# 9Mux_v5.net
KiCad netlist of a schematic drawn in EAGLE
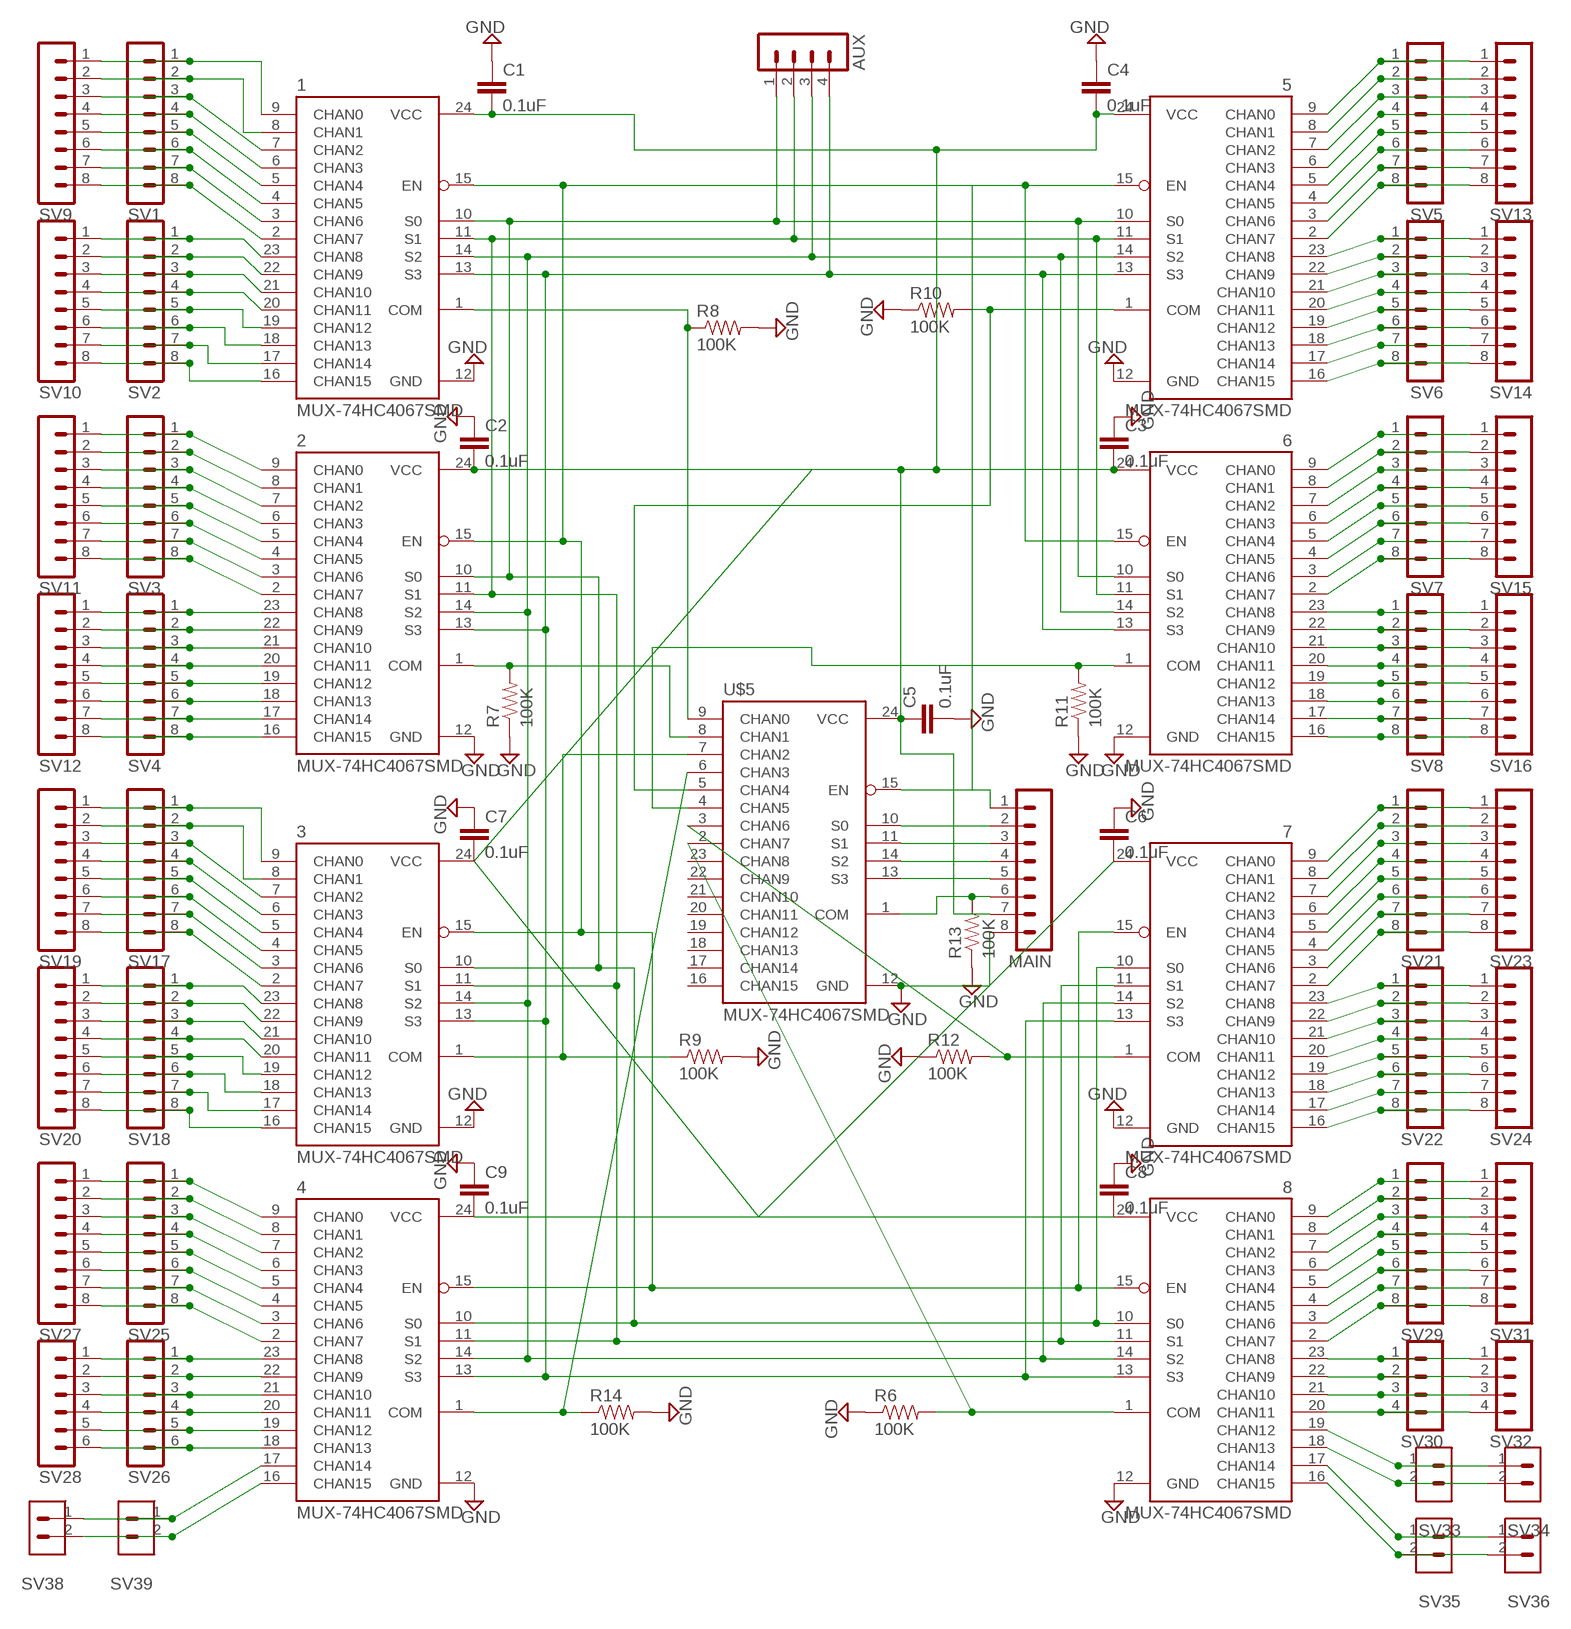
[diagram p0: schematic, sheet 1]

(export (version "E")
  (design (tool "Eeschema 10.0.6"))
  (components
    (comp (ref "1")
      (value "MUX-74HC4067SMD")
      (footprint "eagle-import:SSOP24")
      (libsource (lib "eagle-import") (part "MUX-74HC4067SMD"))
    )
    (comp (ref "2")
      (value "MUX-74HC4067SMD")
      (footprint "eagle-import:SSOP24")
      (libsource (lib "eagle-import") (part "MUX-74HC4067SMD"))
    )
    (comp (ref "3")
      (value "MUX-74HC4067SMD")
      (footprint "eagle-import:SSOP24")
      (libsource (lib "eagle-import") (part "MUX-74HC4067SMD"))
    )
    (comp (ref "4")
      (value "MUX-74HC4067SMD")
      (footprint "eagle-import:SSOP24")
      (libsource (lib "eagle-import") (part "MUX-74HC4067SMD"))
    )
    (comp (ref "5")
      (value "MUX-74HC4067SMD")
      (footprint "eagle-import:SSOP24")
      (libsource (lib "eagle-import") (part "MUX-74HC4067SMD"))
    )
    (comp (ref "6")
      (value "MUX-74HC4067SMD")
      (footprint "eagle-import:SSOP24")
      (libsource (lib "eagle-import") (part "MUX-74HC4067SMD"))
    )
    (comp (ref "7")
      (value "MUX-74HC4067SMD")
      (footprint "eagle-import:SSOP24")
      (libsource (lib "eagle-import") (part "MUX-74HC4067SMD"))
    )
    (comp (ref "8")
      (value "MUX-74HC4067SMD")
      (footprint "eagle-import:SSOP24")
      (libsource (lib "eagle-import") (part "MUX-74HC4067SMD"))
    )
    (comp (ref "AUX")
      (value "MA04-1")
      (footprint "eagle-import:MA04-1")
      (libsource (lib "eagle-import") (part "MA04-1"))
    )
    (comp (ref "C1")
      (value "0.1uF")
      (footprint "eagle-import:0603-CAP")
      (libsource (lib "eagle-import") (part "CAP0603-CAP"))
    )
    (comp (ref "C2")
      (value "0.1uF")
      (footprint "eagle-import:0603-CAP")
      (libsource (lib "eagle-import") (part "CAP0603-CAP"))
    )
    (comp (ref "C3")
      (value "0.1uF")
      (footprint "eagle-import:0603-CAP")
      (libsource (lib "eagle-import") (part "CAP0603-CAP"))
    )
    (comp (ref "C4")
      (value "0.1uF")
      (footprint "eagle-import:0603-CAP")
      (libsource (lib "eagle-import") (part "CAP0603-CAP"))
    )
    (comp (ref "C5")
      (value "0.1uF")
      (footprint "eagle-import:0603-CAP")
      (libsource (lib "eagle-import") (part "CAP0603-CAP"))
    )
    (comp (ref "C6")
      (value "0.1uF")
      (footprint "eagle-import:0603-CAP")
      (libsource (lib "eagle-import") (part "CAP0603-CAP"))
    )
    (comp (ref "C7")
      (value "0.1uF")
      (footprint "eagle-import:0603-CAP")
      (libsource (lib "eagle-import") (part "CAP0603-CAP"))
    )
    (comp (ref "C8")
      (value "0.1uF")
      (footprint "eagle-import:0603-CAP")
      (libsource (lib "eagle-import") (part "CAP0603-CAP"))
    )
    (comp (ref "C9")
      (value "0.1uF")
      (footprint "eagle-import:0603-CAP")
      (libsource (lib "eagle-import") (part "CAP0603-CAP"))
    )
    (comp (ref "MAIN")
      (value "MA08-1")
      (footprint "eagle-import:MA08-1")
      (libsource (lib "eagle-import") (part "MA08-1"))
    )
    (comp (ref "R6")
      (value "100K")
      (footprint "eagle-import:0603-RES")
      (libsource (lib "eagle-import") (part "RESISTOR0603"))
    )
    (comp (ref "R7")
      (value "100K")
      (footprint "eagle-import:0603-RES")
      (libsource (lib "eagle-import") (part "RESISTOR0603"))
    )
    (comp (ref "R8")
      (value "100K")
      (footprint "eagle-import:0603-RES")
      (libsource (lib "eagle-import") (part "RESISTOR0603"))
    )
    (comp (ref "R9")
      (value "100K")
      (footprint "eagle-import:0603-RES")
      (libsource (lib "eagle-import") (part "RESISTOR0603"))
    )
    (comp (ref "R10")
      (value "100K")
      (footprint "eagle-import:0603-RES")
      (libsource (lib "eagle-import") (part "RESISTOR0603"))
    )
    (comp (ref "R11")
      (value "100K")
      (footprint "eagle-import:0603-RES")
      (libsource (lib "eagle-import") (part "RESISTOR0603"))
    )
    (comp (ref "R12")
      (value "100K")
      (footprint "eagle-import:0603-RES")
      (libsource (lib "eagle-import") (part "RESISTOR0603"))
    )
    (comp (ref "R13")
      (value "100K")
      (footprint "eagle-import:0603-RES")
      (libsource (lib "eagle-import") (part "RESISTOR0603"))
    )
    (comp (ref "R14")
      (value "100K")
      (footprint "eagle-import:0603-RES")
      (libsource (lib "eagle-import") (part "RESISTOR0603"))
    )
    (comp (ref "SV1")
      (value "MA08-1")
      (footprint "eagle-import:MA08-1")
      (libsource (lib "eagle-import") (part "MA08-1"))
    )
    (comp (ref "SV2")
      (value "MA08-1")
      (footprint "eagle-import:MA08-1")
      (libsource (lib "eagle-import") (part "MA08-1"))
    )
    (comp (ref "SV3")
      (value "MA08-1")
      (footprint "eagle-import:MA08-1")
      (libsource (lib "eagle-import") (part "MA08-1"))
    )
    (comp (ref "SV4")
      (value "MA08-1")
      (footprint "eagle-import:MA08-1")
      (libsource (lib "eagle-import") (part "MA08-1"))
    )
    (comp (ref "SV5")
      (value "MA08-1")
      (footprint "eagle-import:MA08-1")
      (libsource (lib "eagle-import") (part "MA08-1"))
    )
    (comp (ref "SV6")
      (value "MA08-1")
      (footprint "eagle-import:MA08-1")
      (libsource (lib "eagle-import") (part "MA08-1"))
    )
    (comp (ref "SV7")
      (value "MA08-1")
      (footprint "eagle-import:MA08-1")
      (libsource (lib "eagle-import") (part "MA08-1"))
    )
    (comp (ref "SV8")
      (value "MA08-1")
      (footprint "eagle-import:MA08-1")
      (libsource (lib "eagle-import") (part "MA08-1"))
    )
    (comp (ref "SV9")
      (value "MA08-1")
      (footprint "eagle-import:MA08-1")
      (libsource (lib "eagle-import") (part "MA08-1"))
    )
    (comp (ref "SV10")
      (value "MA08-1")
      (footprint "eagle-import:MA08-1")
      (libsource (lib "eagle-import") (part "MA08-1"))
    )
    (comp (ref "SV11")
      (value "MA08-1")
      (footprint "eagle-import:MA08-1")
      (libsource (lib "eagle-import") (part "MA08-1"))
    )
    (comp (ref "SV12")
      (value "MA08-1")
      (footprint "eagle-import:MA08-1")
      (libsource (lib "eagle-import") (part "MA08-1"))
    )
    (comp (ref "SV13")
      (value "MA08-1")
      (footprint "eagle-import:MA08-1")
      (libsource (lib "eagle-import") (part "MA08-1"))
    )
    (comp (ref "SV14")
      (value "MA08-1")
      (footprint "eagle-import:MA08-1")
      (libsource (lib "eagle-import") (part "MA08-1"))
    )
    (comp (ref "SV15")
      (value "MA08-1")
      (footprint "eagle-import:MA08-1")
      (libsource (lib "eagle-import") (part "MA08-1"))
    )
    (comp (ref "SV16")
      (value "MA08-1")
      (footprint "eagle-import:MA08-1")
      (libsource (lib "eagle-import") (part "MA08-1"))
    )
    (comp (ref "SV17")
      (value "MA08-1")
      (footprint "eagle-import:MA08-1")
      (libsource (lib "eagle-import") (part "MA08-1"))
    )
    (comp (ref "SV18")
      (value "MA08-1")
      (footprint "eagle-import:MA08-1")
      (libsource (lib "eagle-import") (part "MA08-1"))
    )
    (comp (ref "SV19")
      (value "MA08-1")
      (footprint "eagle-import:MA08-1")
      (libsource (lib "eagle-import") (part "MA08-1"))
    )
    (comp (ref "SV20")
      (value "MA08-1")
      (footprint "eagle-import:MA08-1")
      (libsource (lib "eagle-import") (part "MA08-1"))
    )
    (comp (ref "SV21")
      (value "MA08-1")
      (footprint "eagle-import:MA08-1")
      (libsource (lib "eagle-import") (part "MA08-1"))
    )
    (comp (ref "SV22")
      (value "MA08-1")
      (footprint "eagle-import:MA08-1")
      (libsource (lib "eagle-import") (part "MA08-1"))
    )
    (comp (ref "SV23")
      (value "MA08-1")
      (footprint "eagle-import:MA08-1")
      (libsource (lib "eagle-import") (part "MA08-1"))
    )
    (comp (ref "SV24")
      (value "MA08-1")
      (footprint "eagle-import:MA08-1")
      (libsource (lib "eagle-import") (part "MA08-1"))
    )
    (comp (ref "SV25")
      (value "MA08-1")
      (footprint "eagle-import:MA08-1")
      (libsource (lib "eagle-import") (part "MA08-1"))
    )
    (comp (ref "SV26")
      (value "MA06-1")
      (footprint "eagle-import:MA06-1")
      (libsource (lib "eagle-import") (part "MA06-1"))
    )
    (comp (ref "SV27")
      (value "MA08-1")
      (footprint "eagle-import:MA08-1")
      (libsource (lib "eagle-import") (part "MA08-1"))
    )
    (comp (ref "SV28")
      (value "MA06-1")
      (footprint "eagle-import:MA06-1")
      (libsource (lib "eagle-import") (part "MA06-1"))
    )
    (comp (ref "SV29")
      (value "MA08-1")
      (footprint "eagle-import:MA08-1")
      (libsource (lib "eagle-import") (part "MA08-1"))
    )
    (comp (ref "SV30")
      (value "MA04-1")
      (footprint "eagle-import:MA04-1")
      (libsource (lib "eagle-import") (part "MA04-1"))
    )
    (comp (ref "SV31")
      (value "MA08-1")
      (footprint "eagle-import:MA08-1")
      (libsource (lib "eagle-import") (part "MA08-1"))
    )
    (comp (ref "SV32")
      (value "MA04-1")
      (footprint "eagle-import:MA04-1")
      (libsource (lib "eagle-import") (part "MA04-1"))
    )
    (comp (ref "SV33")
      (value "MA02-1")
      (footprint "eagle-import:MA03-1")
      (libsource (lib "eagle-import") (part "MA02-1"))
    )
    (comp (ref "SV34")
      (value "MA02-1")
      (footprint "eagle-import:MA03-1")
      (libsource (lib "eagle-import") (part "MA02-1"))
    )
    (comp (ref "SV35")
      (value "MA02-1")
      (footprint "eagle-import:MA03-1")
      (libsource (lib "eagle-import") (part "MA02-1"))
    )
    (comp (ref "SV36")
      (value "MA02-1")
      (footprint "eagle-import:MA03-1")
      (libsource (lib "eagle-import") (part "MA02-1"))
    )
    (comp (ref "SV38")
      (value "MA02-1")
      (footprint "eagle-import:MA03-1")
      (libsource (lib "eagle-import") (part "MA02-1"))
    )
    (comp (ref "SV39")
      (value "MA02-1")
      (footprint "eagle-import:MA03-1")
      (libsource (lib "eagle-import") (part "MA02-1"))
    )
    (comp (ref "U$5")
      (value "MUX-74HC4067SMD")
      (footprint "eagle-import:SSOP24")
      (libsource (lib "eagle-import") (part "MUX-74HC4067SMD"))
    )
  )
  (nets
    (net (code "1") (name "GND") (class "Default")
      (node (ref "1") (pin "12") (pinfunction "GND_12") (pintype "bidirectional"))
      (node (ref "2") (pin "12") (pinfunction "GND_12") (pintype "bidirectional"))
      (node (ref "3") (pin "12") (pinfunction "GND_12") (pintype "bidirectional"))
      (node (ref "4") (pin "12") (pinfunction "GND_12") (pintype "bidirectional"))
      (node (ref "5") (pin "12") (pinfunction "GND_12") (pintype "bidirectional"))
      (node (ref "6") (pin "12") (pinfunction "GND_12") (pintype "bidirectional"))
      (node (ref "7") (pin "12") (pinfunction "GND_12") (pintype "bidirectional"))
      (node (ref "8") (pin "12") (pinfunction "GND_12") (pintype "bidirectional"))
      (node (ref "C1") (pin "1") (pinfunction "1_1") (pintype "passive"))
      (node (ref "C2") (pin "1") (pinfunction "1_1") (pintype "passive"))
      (node (ref "C3") (pin "1") (pinfunction "1_1") (pintype "passive"))
      (node (ref "C4") (pin "1") (pinfunction "1_1") (pintype "passive"))
      (node (ref "C5") (pin "2") (pinfunction "2_2") (pintype "passive"))
      (node (ref "C6") (pin "1") (pinfunction "1_1") (pintype "passive"))
      (node (ref "C7") (pin "1") (pinfunction "1_1") (pintype "passive"))
      (node (ref "C8") (pin "1") (pinfunction "1_1") (pintype "passive"))
      (node (ref "C9") (pin "1") (pinfunction "1_1") (pintype "passive"))
      (node (ref "MAIN") (pin "8") (pinfunction "8_8") (pintype "passive"))
      (node (ref "R10") (pin "1") (pinfunction "1_1") (pintype "passive"))
      (node (ref "R11") (pin "1") (pinfunction "1_1") (pintype "passive"))
      (node (ref "R12") (pin "1") (pinfunction "1_1") (pintype "passive"))
      (node (ref "R13") (pin "1") (pinfunction "1_1") (pintype "passive"))
      (node (ref "R14") (pin "2") (pinfunction "2_2") (pintype "passive"))
      (node (ref "R6") (pin "1") (pinfunction "1_1") (pintype "passive"))
      (node (ref "R7") (pin "1") (pinfunction "1_1") (pintype "passive"))
      (node (ref "R8") (pin "2") (pinfunction "2_2") (pintype "passive"))
      (node (ref "R9") (pin "2") (pinfunction "2_2") (pintype "passive"))
      (node (ref "U$5") (pin "12") (pinfunction "GND_12") (pintype "bidirectional"))
    )
    (net (code "2") (name "Net-(1-CHAN0)") (class "Default")
      (node (ref "1") (pin "9") (pinfunction "CHAN0_9") (pintype "bidirectional"))
      (node (ref "SV1") (pin "1") (pinfunction "1_1") (pintype "passive"))
      (node (ref "SV9") (pin "1") (pinfunction "1_1") (pintype "passive"))
    )
    (net (code "3") (name "Net-(1-CHAN1)") (class "Default")
      (node (ref "1") (pin "8") (pinfunction "CHAN1_8") (pintype "bidirectional"))
      (node (ref "SV1") (pin "2") (pinfunction "2_2") (pintype "passive"))
      (node (ref "SV9") (pin "2") (pinfunction "2_2") (pintype "passive"))
    )
    (net (code "4") (name "Net-(1-CHAN2)") (class "Default")
      (node (ref "1") (pin "7") (pinfunction "CHAN2_7") (pintype "bidirectional"))
      (node (ref "SV1") (pin "3") (pinfunction "3_3") (pintype "passive"))
      (node (ref "SV9") (pin "3") (pinfunction "3_3") (pintype "passive"))
    )
    (net (code "5") (name "Net-(1-CHAN3)") (class "Default")
      (node (ref "1") (pin "6") (pinfunction "CHAN3_6") (pintype "bidirectional"))
      (node (ref "SV1") (pin "4") (pinfunction "4_4") (pintype "passive"))
      (node (ref "SV9") (pin "4") (pinfunction "4_4") (pintype "passive"))
    )
    (net (code "6") (name "Net-(1-CHAN4)") (class "Default")
      (node (ref "1") (pin "5") (pinfunction "CHAN4_5") (pintype "bidirectional"))
      (node (ref "SV1") (pin "5") (pinfunction "5_5") (pintype "passive"))
      (node (ref "SV9") (pin "5") (pinfunction "5_5") (pintype "passive"))
    )
    (net (code "7") (name "Net-(1-CHAN5)") (class "Default")
      (node (ref "1") (pin "4") (pinfunction "CHAN5_4") (pintype "bidirectional"))
      (node (ref "SV1") (pin "6") (pinfunction "6_6") (pintype "passive"))
      (node (ref "SV9") (pin "6") (pinfunction "6_6") (pintype "passive"))
    )
    (net (code "8") (name "Net-(1-CHAN6)") (class "Default")
      (node (ref "1") (pin "3") (pinfunction "CHAN6_3") (pintype "bidirectional"))
      (node (ref "SV1") (pin "7") (pinfunction "7_7") (pintype "passive"))
      (node (ref "SV9") (pin "7") (pinfunction "7_7") (pintype "passive"))
    )
    (net (code "9") (name "Net-(1-CHAN7)") (class "Default")
      (node (ref "1") (pin "2") (pinfunction "CHAN7_2") (pintype "bidirectional"))
      (node (ref "SV1") (pin "8") (pinfunction "8_8") (pintype "passive"))
      (node (ref "SV9") (pin "8") (pinfunction "8_8") (pintype "passive"))
    )
    (net (code "10") (name "Net-(1-CHAN8)") (class "Default")
      (node (ref "1") (pin "23") (pinfunction "CHAN8_23") (pintype "bidirectional"))
      (node (ref "SV10") (pin "1") (pinfunction "1_1") (pintype "passive"))
      (node (ref "SV2") (pin "1") (pinfunction "1_1") (pintype "passive"))
    )
    (net (code "11") (name "Net-(1-CHAN9)") (class "Default")
      (node (ref "1") (pin "22") (pinfunction "CHAN9_22") (pintype "bidirectional"))
      (node (ref "SV10") (pin "2") (pinfunction "2_2") (pintype "passive"))
      (node (ref "SV2") (pin "2") (pinfunction "2_2") (pintype "passive"))
    )
    (net (code "12") (name "Net-(1-CHAN10)") (class "Default")
      (node (ref "1") (pin "21") (pinfunction "CHAN10_21") (pintype "bidirectional"))
      (node (ref "SV10") (pin "3") (pinfunction "3_3") (pintype "passive"))
      (node (ref "SV2") (pin "3") (pinfunction "3_3") (pintype "passive"))
    )
    (net (code "13") (name "Net-(1-CHAN11)") (class "Default")
      (node (ref "1") (pin "20") (pinfunction "CHAN11_20") (pintype "bidirectional"))
      (node (ref "SV10") (pin "4") (pinfunction "4_4") (pintype "passive"))
      (node (ref "SV2") (pin "4") (pinfunction "4_4") (pintype "passive"))
    )
    (net (code "14") (name "Net-(1-CHAN12)") (class "Default")
      (node (ref "1") (pin "19") (pinfunction "CHAN12_19") (pintype "bidirectional"))
      (node (ref "SV10") (pin "5") (pinfunction "5_5") (pintype "passive"))
      (node (ref "SV2") (pin "5") (pinfunction "5_5") (pintype "passive"))
    )
    (net (code "15") (name "Net-(1-CHAN13)") (class "Default")
      (node (ref "1") (pin "18") (pinfunction "CHAN13_18") (pintype "bidirectional"))
      (node (ref "SV10") (pin "6") (pinfunction "6_6") (pintype "passive"))
      (node (ref "SV2") (pin "6") (pinfunction "6_6") (pintype "passive"))
    )
    (net (code "16") (name "Net-(1-CHAN14)") (class "Default")
      (node (ref "1") (pin "17") (pinfunction "CHAN14_17") (pintype "bidirectional"))
      (node (ref "SV10") (pin "7") (pinfunction "7_7") (pintype "passive"))
      (node (ref "SV2") (pin "7") (pinfunction "7_7") (pintype "passive"))
    )
    (net (code "17") (name "Net-(1-CHAN15)") (class "Default")
      (node (ref "1") (pin "16") (pinfunction "CHAN15_16") (pintype "bidirectional"))
      (node (ref "SV10") (pin "8") (pinfunction "8_8") (pintype "passive"))
      (node (ref "SV2") (pin "8") (pinfunction "8_8") (pintype "passive"))
    )
    (net (code "18") (name "Net-(1-COM)") (class "Default")
      (node (ref "1") (pin "1") (pinfunction "COM_1") (pintype "bidirectional"))
      (node (ref "R8") (pin "1") (pinfunction "1_1") (pintype "passive"))
      (node (ref "U$5") (pin "9") (pinfunction "CHAN0_9") (pintype "bidirectional"))
    )
    (net (code "19") (name "Net-(1-EN)") (class "Default")
      (node (ref "1") (pin "15") (pinfunction "EN_15") (pintype "input"))
      (node (ref "2") (pin "15") (pinfunction "EN_15") (pintype "input"))
      (node (ref "3") (pin "15") (pinfunction "EN_15") (pintype "input"))
      (node (ref "4") (pin "15") (pinfunction "EN_15") (pintype "input"))
      (node (ref "5") (pin "15") (pinfunction "EN_15") (pintype "input"))
      (node (ref "6") (pin "15") (pinfunction "EN_15") (pintype "input"))
      (node (ref "7") (pin "15") (pinfunction "EN_15") (pintype "input"))
      (node (ref "8") (pin "15") (pinfunction "EN_15") (pintype "input"))
      (node (ref "MAIN") (pin "1") (pinfunction "1_1") (pintype "passive"))
      (node (ref "U$5") (pin "15") (pinfunction "EN_15") (pintype "input"))
    )
    (net (code "20") (name "Net-(1-S0)") (class "Default")
      (node (ref "1") (pin "10") (pinfunction "S0_10") (pintype "input"))
      (node (ref "2") (pin "10") (pinfunction "S0_10") (pintype "input"))
      (node (ref "3") (pin "10") (pinfunction "S0_10") (pintype "input"))
      (node (ref "4") (pin "10") (pinfunction "S0_10") (pintype "input"))
      (node (ref "5") (pin "10") (pinfunction "S0_10") (pintype "input"))
      (node (ref "6") (pin "10") (pinfunction "S0_10") (pintype "input"))
      (node (ref "7") (pin "10") (pinfunction "S0_10") (pintype "input"))
      (node (ref "8") (pin "10") (pinfunction "S0_10") (pintype "input"))
      (node (ref "AUX") (pin "1") (pinfunction "1_1") (pintype "passive"))
    )
    (net (code "21") (name "Net-(1-S1)") (class "Default")
      (node (ref "1") (pin "11") (pinfunction "S1_11") (pintype "input"))
      (node (ref "2") (pin "11") (pinfunction "S1_11") (pintype "input"))
      (node (ref "3") (pin "11") (pinfunction "S1_11") (pintype "input"))
      (node (ref "4") (pin "11") (pinfunction "S1_11") (pintype "input"))
      (node (ref "5") (pin "11") (pinfunction "S1_11") (pintype "input"))
      (node (ref "6") (pin "11") (pinfunction "S1_11") (pintype "input"))
      (node (ref "7") (pin "11") (pinfunction "S1_11") (pintype "input"))
      (node (ref "8") (pin "11") (pinfunction "S1_11") (pintype "input"))
      (node (ref "AUX") (pin "2") (pinfunction "2_2") (pintype "passive"))
    )
    (net (code "22") (name "Net-(1-S2)") (class "Default")
      (node (ref "1") (pin "14") (pinfunction "S2_14") (pintype "input"))
      (node (ref "2") (pin "14") (pinfunction "S2_14") (pintype "input"))
      (node (ref "3") (pin "14") (pinfunction "S2_14") (pintype "input"))
      (node (ref "4") (pin "14") (pinfunction "S2_14") (pintype "input"))
      (node (ref "5") (pin "14") (pinfunction "S2_14") (pintype "input"))
      (node (ref "6") (pin "14") (pinfunction "S2_14") (pintype "input"))
      (node (ref "7") (pin "14") (pinfunction "S2_14") (pintype "input"))
      (node (ref "8") (pin "14") (pinfunction "S2_14") (pintype "input"))
      (node (ref "AUX") (pin "3") (pinfunction "3_3") (pintype "passive"))
    )
    (net (code "23") (name "Net-(1-S3)") (class "Default")
      (node (ref "1") (pin "13") (pinfunction "S3_13") (pintype "input"))
      (node (ref "2") (pin "13") (pinfunction "S3_13") (pintype "input"))
      (node (ref "3") (pin "13") (pinfunction "S3_13") (pintype "input"))
      (node (ref "4") (pin "13") (pinfunction "S3_13") (pintype "input"))
      (node (ref "5") (pin "13") (pinfunction "S3_13") (pintype "input"))
      (node (ref "6") (pin "13") (pinfunction "S3_13") (pintype "input"))
      (node (ref "7") (pin "13") (pinfunction "S3_13") (pintype "input"))
      (node (ref "8") (pin "13") (pinfunction "S3_13") (pintype "input"))
      (node (ref "AUX") (pin "4") (pinfunction "4_4") (pintype "passive"))
    )
    (net (code "24") (name "Net-(1-VCC)") (class "Default")
      (node (ref "1") (pin "24") (pinfunction "VCC_24") (pintype "bidirectional"))
      (node (ref "2") (pin "24") (pinfunction "VCC_24") (pintype "bidirectional"))
      (node (ref "3") (pin "24") (pinfunction "VCC_24") (pintype "bidirectional"))
      (node (ref "4") (pin "24") (pinfunction "VCC_24") (pintype "bidirectional"))
      (node (ref "5") (pin "24") (pinfunction "VCC_24") (pintype "bidirectional"))
      (node (ref "6") (pin "24") (pinfunction "VCC_24") (pintype "bidirectional"))
      (node (ref "7") (pin "24") (pinfunction "VCC_24") (pintype "bidirectional"))
      (node (ref "8") (pin "24") (pinfunction "VCC_24") (pintype "bidirectional"))
      (node (ref "C1") (pin "2") (pinfunction "2_2") (pintype "passive"))
      (node (ref "C2") (pin "2") (pinfunction "2_2") (pintype "passive"))
      (node (ref "C3") (pin "2") (pinfunction "2_2") (pintype "passive"))
      (node (ref "C4") (pin "2") (pinfunction "2_2") (pintype "passive"))
      (node (ref "C5") (pin "1") (pinfunction "1_1") (pintype "passive"))
      (node (ref "C6") (pin "2") (pinfunction "2_2") (pintype "passive"))
      (node (ref "C7") (pin "2") (pinfunction "2_2") (pintype "passive"))
      (node (ref "C8") (pin "2") (pinfunction "2_2") (pintype "passive"))
      (node (ref "C9") (pin "2") (pinfunction "2_2") (pintype "passive"))
      (node (ref "MAIN") (pin "7") (pinfunction "7_7") (pintype "passive"))
      (node (ref "U$5") (pin "24") (pinfunction "VCC_24") (pintype "bidirectional"))
    )
    (net (code "25") (name "Net-(2-CHAN0)") (class "Default")
      (node (ref "2") (pin "9") (pinfunction "CHAN0_9") (pintype "bidirectional"))
      (node (ref "SV11") (pin "1") (pinfunction "1_1") (pintype "passive"))
      (node (ref "SV3") (pin "1") (pinfunction "1_1") (pintype "passive"))
    )
    (net (code "26") (name "Net-(2-CHAN1)") (class "Default")
      (node (ref "2") (pin "8") (pinfunction "CHAN1_8") (pintype "bidirectional"))
      (node (ref "SV11") (pin "2") (pinfunction "2_2") (pintype "passive"))
      (node (ref "SV3") (pin "2") (pinfunction "2_2") (pintype "passive"))
    )
    (net (code "27") (name "Net-(2-CHAN2)") (class "Default")
      (node (ref "2") (pin "7") (pinfunction "CHAN2_7") (pintype "bidirectional"))
      (node (ref "SV11") (pin "3") (pinfunction "3_3") (pintype "passive"))
      (node (ref "SV3") (pin "3") (pinfunction "3_3") (pintype "passive"))
    )
    (net (code "28") (name "Net-(2-CHAN3)") (class "Default")
      (node (ref "2") (pin "6") (pinfunction "CHAN3_6") (pintype "bidirectional"))
      (node (ref "SV11") (pin "4") (pinfunction "4_4") (pintype "passive"))
      (node (ref "SV3") (pin "4") (pinfunction "4_4") (pintype "passive"))
    )
    (net (code "29") (name "Net-(2-CHAN4)") (class "Default")
      (node (ref "2") (pin "5") (pinfunction "CHAN4_5") (pintype "bidirectional"))
      (node (ref "SV11") (pin "5") (pinfunction "5_5") (pintype "passive"))
      (node (ref "SV3") (pin "5") (pinfunction "5_5") (pintype "passive"))
    )
    (net (code "30") (name "Net-(2-CHAN5)") (class "Default")
      (node (ref "2") (pin "4") (pinfunction "CHAN5_4") (pintype "bidirectional"))
      (node (ref "SV11") (pin "6") (pinfunction "6_6") (pintype "passive"))
      (node (ref "SV3") (pin "6") (pinfunction "6_6") (pintype "passive"))
    )
    (net (code "31") (name "Net-(2-CHAN6)") (class "Default")
      (node (ref "2") (pin "3") (pinfunction "CHAN6_3") (pintype "bidirectional"))
      (node (ref "SV11") (pin "7") (pinfunction "7_7") (pintype "passive"))
      (node (ref "SV3") (pin "7") (pinfunction "7_7") (pintype "passive"))
    )
    (net (code "32") (name "Net-(2-CHAN7)") (class "Default")
      (node (ref "2") (pin "2") (pinfunction "CHAN7_2") (pintype "bidirectional"))
      (node (ref "SV11") (pin "8") (pinfunction "8_8") (pintype "passive"))
      (node (ref "SV3") (pin "8") (pinfunction "8_8") (pintype "passive"))
    )
    (net (code "33") (name "Net-(2-CHAN8)") (class "Default")
      (node (ref "2") (pin "23") (pinfunction "CHAN8_23") (pintype "bidirectional"))
      (node (ref "SV12") (pin "1") (pinfunction "1_1") (pintype "passive"))
      (node (ref "SV4") (pin "1") (pinfunction "1_1") (pintype "passive"))
    )
    (net (code "34") (name "Net-(2-CHAN9)") (class "Default")
      (node (ref "2") (pin "22") (pinfunction "CHAN9_22") (pintype "bidirectional"))
      (node (ref "SV12") (pin "2") (pinfunction "2_2") (pintype "passive"))
      (node (ref "SV4") (pin "2") (pinfunction "2_2") (pintype "passive"))
    )
    (net (code "35") (name "Net-(2-CHAN10)") (class "Default")
      (node (ref "2") (pin "21") (pinfunction "CHAN10_21") (pintype "bidirectional"))
      (node (ref "SV12") (pin "3") (pinfunction "3_3") (pintype "passive"))
      (node (ref "SV4") (pin "3") (pinfunction "3_3") (pintype "passive"))
    )
    (net (code "36") (name "Net-(2-CHAN11)") (class "Default")
      (node (ref "2") (pin "20") (pinfunction "CHAN11_20") (pintype "bidirectional"))
      (node (ref "SV12") (pin "4") (pinfunction "4_4") (pintype "passive"))
      (node (ref "SV4") (pin "4") (pinfunction "4_4") (pintype "passive"))
    )
    (net (code "37") (name "Net-(2-CHAN12)") (class "Default")
      (node (ref "2") (pin "19") (pinfunction "CHAN12_19") (pintype "bidirectional"))
      (node (ref "SV12") (pin "5") (pinfunction "5_5") (pintype "passive"))
      (node (ref "SV4") (pin "5") (pinfunction "5_5") (pintype "passive"))
    )
    (net (code "38") (name "Net-(2-CHAN13)") (class "Default")
      (node (ref "2") (pin "18") (pinfunction "CHAN13_18") (pintype "bidirectional"))
      (node (ref "SV12") (pin "6") (pinfunction "6_6") (pintype "passive"))
      (node (ref "SV4") (pin "6") (pinfunction "6_6") (pintype "passive"))
    )
    (net (code "39") (name "Net-(2-CHAN14)") (class "Default")
      (node (ref "2") (pin "17") (pinfunction "CHAN14_17") (pintype "bidirectional"))
      (node (ref "SV12") (pin "7") (pinfunction "7_7") (pintype "passive"))
      (node (ref "SV4") (pin "7") (pinfunction "7_7") (pintype "passive"))
    )
    (net (code "40") (name "Net-(2-CHAN15)") (class "Default")
      (node (ref "2") (pin "16") (pinfunction "CHAN15_16") (pintype "bidirectional"))
      (node (ref "SV12") (pin "8") (pinfunction "8_8") (pintype "passive"))
      (node (ref "SV4") (pin "8") (pinfunction "8_8") (pintype "passive"))
    )
    (net (code "41") (name "Net-(2-COM)") (class "Default")
      (node (ref "2") (pin "1") (pinfunction "COM_1") (pintype "bidirectional"))
      (node (ref "R7") (pin "2") (pinfunction "2_2") (pintype "passive"))
      (node (ref "U$5") (pin "8") (pinfunction "CHAN1_8") (pintype "bidirectional"))
    )
    (net (code "42") (name "Net-(3-CHAN0)") (class "Default")
      (node (ref "3") (pin "9") (pinfunction "CHAN0_9") (pintype "bidirectional"))
      (node (ref "SV17") (pin "1") (pinfunction "1_1") (pintype "passive"))
      (node (ref "SV19") (pin "1") (pinfunction "1_1") (pintype "passive"))
    )
    (net (code "43") (name "Net-(3-CHAN1)") (class "Default")
      (node (ref "3") (pin "8") (pinfunction "CHAN1_8") (pintype "bidirectional"))
      (node (ref "SV17") (pin "2") (pinfunction "2_2") (pintype "passive"))
      (node (ref "SV19") (pin "2") (pinfunction "2_2") (pintype "passive"))
    )
    (net (code "44") (name "Net-(3-CHAN2)") (class "Default")
      (node (ref "3") (pin "7") (pinfunction "CHAN2_7") (pintype "bidirectional"))
      (node (ref "SV17") (pin "3") (pinfunction "3_3") (pintype "passive"))
      (node (ref "SV19") (pin "3") (pinfunction "3_3") (pintype "passive"))
    )
    (net (code "45") (name "Net-(3-CHAN3)") (class "Default")
      (node (ref "3") (pin "6") (pinfunction "CHAN3_6") (pintype "bidirectional"))
      (node (ref "SV17") (pin "4") (pinfunction "4_4") (pintype "passive"))
      (node (ref "SV19") (pin "4") (pinfunction "4_4") (pintype "passive"))
    )
    (net (code "46") (name "Net-(3-CHAN4)") (class "Default")
      (node (ref "3") (pin "5") (pinfunction "CHAN4_5") (pintype "bidirectional"))
      (node (ref "SV17") (pin "5") (pinfunction "5_5") (pintype "passive"))
      (node (ref "SV19") (pin "5") (pinfunction "5_5") (pintype "passive"))
    )
    (net (code "47") (name "Net-(3-CHAN5)") (class "Default")
      (node (ref "3") (pin "4") (pinfunction "CHAN5_4") (pintype "bidirectional"))
      (node (ref "SV17") (pin "6") (pinfunction "6_6") (pintype "passive"))
      (node (ref "SV19") (pin "6") (pinfunction "6_6") (pintype "passive"))
    )
    (net (code "48") (name "Net-(3-CHAN6)") (class "Default")
      (node (ref "3") (pin "3") (pinfunction "CHAN6_3") (pintype "bidirectional"))
      (node (ref "SV17") (pin "7") (pinfunction "7_7") (pintype "passive"))
      (node (ref "SV19") (pin "7") (pinfunction "7_7") (pintype "passive"))
    )
    (net (code "49") (name "Net-(3-CHAN7)") (class "Default")
      (node (ref "3") (pin "2") (pinfunction "CHAN7_2") (pintype "bidirectional"))
      (node (ref "SV17") (pin "8") (pinfunction "8_8") (pintype "passive"))
      (node (ref "SV19") (pin "8") (pinfunction "8_8") (pintype "passive"))
    )
    (net (code "50") (name "Net-(3-CHAN8)") (class "Default")
      (node (ref "3") (pin "23") (pinfunction "CHAN8_23") (pintype "bidirectional"))
      (node (ref "SV18") (pin "1") (pinfunction "1_1") (pintype "passive"))
      (node (ref "SV20") (pin "1") (pinfunction "1_1") (pintype "passive"))
    )
    (net (code "51") (name "Net-(3-CHAN9)") (class "Default")
      (node (ref "3") (pin "22") (pinfunction "CHAN9_22") (pintype "bidirectional"))
      (node (ref "SV18") (pin "2") (pinfunction "2_2") (pintype "passive"))
      (node (ref "SV20") (pin "2") (pinfunction "2_2") (pintype "passive"))
    )
    (net (code "52") (name "Net-(3-CHAN10)") (class "Default")
      (node (ref "3") (pin "21") (pinfunction "CHAN10_21") (pintype "bidirectional"))
      (node (ref "SV18") (pin "3") (pinfunction "3_3") (pintype "passive"))
      (node (ref "SV20") (pin "3") (pinfunction "3_3") (pintype "passive"))
    )
    (net (code "53") (name "Net-(3-CHAN11)") (class "Default")
      (node (ref "3") (pin "20") (pinfunction "CHAN11_20") (pintype "bidirectional"))
      (node (ref "SV18") (pin "4") (pinfunction "4_4") (pintype "passive"))
      (node (ref "SV20") (pin "4") (pinfunction "4_4") (pintype "passive"))
    )
    (net (code "54") (name "Net-(3-CHAN12)") (class "Default")
      (node (ref "3") (pin "19") (pinfunction "CHAN12_19") (pintype "bidirectional"))
      (node (ref "SV18") (pin "5") (pinfunction "5_5") (pintype "passive"))
      (node (ref "SV20") (pin "5") (pinfunction "5_5") (pintype "passive"))
    )
    (net (code "55") (name "Net-(3-CHAN13)") (class "Default")
      (node (ref "3") (pin "18") (pinfunction "CHAN13_18") (pintype "bidirectional"))
      (node (ref "SV18") (pin "6") (pinfunction "6_6") (pintype "passive"))
      (node (ref "SV20") (pin "6") (pinfunction "6_6") (pintype "passive"))
    )
    (net (code "56") (name "Net-(3-CHAN14)") (class "Default")
      (node (ref "3") (pin "17") (pinfunction "CHAN14_17") (pintype "bidirectional"))
      (node (ref "SV18") (pin "7") (pinfunction "7_7") (pintype "passive"))
      (node (ref "SV20") (pin "7") (pinfunction "7_7") (pintype "passive"))
    )
    (net (code "57") (name "Net-(3-CHAN15)") (class "Default")
      (node (ref "3") (pin "16") (pinfunction "CHAN15_16") (pintype "bidirectional"))
      (node (ref "SV18") (pin "8") (pinfunction "8_8") (pintype "passive"))
      (node (ref "SV20") (pin "8") (pinfunction "8_8") (pintype "passive"))
    )
    (net (code "58") (name "Net-(3-COM)") (class "Default")
      (node (ref "3") (pin "1") (pinfunction "COM_1") (pintype "bidirectional"))
      (node (ref "R9") (pin "1") (pinfunction "1_1") (pintype "passive"))
      (node (ref "U$5") (pin "7") (pinfunction "CHAN2_7") (pintype "bidirectional"))
    )
    (net (code "59") (name "Net-(4-CHAN0)") (class "Default")
      (node (ref "4") (pin "9") (pinfunction "CHAN0_9") (pintype "bidirectional"))
      (node (ref "SV25") (pin "1") (pinfunction "1_1") (pintype "passive"))
      (node (ref "SV27") (pin "1") (pinfunction "1_1") (pintype "passive"))
    )
    (net (code "60") (name "Net-(4-CHAN1)") (class "Default")
      (node (ref "4") (pin "8") (pinfunction "CHAN1_8") (pintype "bidirectional"))
      (node (ref "SV25") (pin "2") (pinfunction "2_2") (pintype "passive"))
      (node (ref "SV27") (pin "2") (pinfunction "2_2") (pintype "passive"))
    )
    (net (code "61") (name "Net-(4-CHAN2)") (class "Default")
      (node (ref "4") (pin "7") (pinfunction "CHAN2_7") (pintype "bidirectional"))
      (node (ref "SV25") (pin "3") (pinfunction "3_3") (pintype "passive"))
      (node (ref "SV27") (pin "3") (pinfunction "3_3") (pintype "passive"))
    )
    (net (code "62") (name "Net-(4-CHAN3)") (class "Default")
      (node (ref "4") (pin "6") (pinfunction "CHAN3_6") (pintype "bidirectional"))
      (node (ref "SV25") (pin "4") (pinfunction "4_4") (pintype "passive"))
      (node (ref "SV27") (pin "4") (pinfunction "4_4") (pintype "passive"))
    )
    (net (code "63") (name "Net-(4-CHAN4)") (class "Default")
      (node (ref "4") (pin "5") (pinfunction "CHAN4_5") (pintype "bidirectional"))
      (node (ref "SV25") (pin "5") (pinfunction "5_5") (pintype "passive"))
      (node (ref "SV27") (pin "5") (pinfunction "5_5") (pintype "passive"))
    )
    (net (code "64") (name "Net-(4-CHAN5)") (class "Default")
      (node (ref "4") (pin "4") (pinfunction "CHAN5_4") (pintype "bidirectional"))
      (node (ref "SV25") (pin "6") (pinfunction "6_6") (pintype "passive"))
      (node (ref "SV27") (pin "6") (pinfunction "6_6") (pintype "passive"))
    )
    (net (code "65") (name "Net-(4-CHAN6)") (class "Default")
      (node (ref "4") (pin "3") (pinfunction "CHAN6_3") (pintype "bidirectional"))
      (node (ref "SV25") (pin "7") (pinfunction "7_7") (pintype "passive"))
      (node (ref "SV27") (pin "7") (pinfunction "7_7") (pintype "passive"))
    )
    (net (code "66") (name "Net-(4-CHAN7)") (class "Default")
      (node (ref "4") (pin "2") (pinfunction "CHAN7_2") (pintype "bidirectional"))
      (node (ref "SV25") (pin "8") (pinfunction "8_8") (pintype "passive"))
      (node (ref "SV27") (pin "8") (pinfunction "8_8") (pintype "passive"))
    )
    (net (code "67") (name "Net-(4-CHAN8)") (class "Default")
      (node (ref "4") (pin "23") (pinfunction "CHAN8_23") (pintype "bidirectional"))
      (node (ref "SV26") (pin "1") (pinfunction "1_1") (pintype "passive"))
      (node (ref "SV28") (pin "1") (pinfunction "1_1") (pintype "passive"))
    )
    (net (code "68") (name "Net-(4-CHAN9)") (class "Default")
      (node (ref "4") (pin "22") (pinfunction "CHAN9_22") (pintype "bidirectional"))
      (node (ref "SV26") (pin "2") (pinfunction "2_2") (pintype "passive"))
      (node (ref "SV28") (pin "2") (pinfunction "2_2") (pintype "passive"))
    )
    (net (code "69") (name "Net-(4-CHAN10)") (class "Default")
      (node (ref "4") (pin "21") (pinfunction "CHAN10_21") (pintype "bidirectional"))
      (node (ref "SV26") (pin "3") (pinfunction "3_3") (pintype "passive"))
      (node (ref "SV28") (pin "3") (pinfunction "3_3") (pintype "passive"))
    )
    (net (code "70") (name "Net-(4-CHAN11)") (class "Default")
      (node (ref "4") (pin "20") (pinfunction "CHAN11_20") (pintype "bidirectional"))
      (node (ref "SV26") (pin "4") (pinfunction "4_4") (pintype "passive"))
      (node (ref "SV28") (pin "4") (pinfunction "4_4") (pintype "passive"))
    )
    (net (code "71") (name "Net-(4-CHAN12)") (class "Default")
      (node (ref "4") (pin "19") (pinfunction "CHAN12_19") (pintype "bidirectional"))
      (node (ref "SV26") (pin "5") (pinfunction "5_5") (pintype "passive"))
      (node (ref "SV28") (pin "5") (pinfunction "5_5") (pintype "passive"))
    )
    (net (code "72") (name "Net-(4-CHAN13)") (class "Default")
      (node (ref "4") (pin "18") (pinfunction "CHAN13_18") (pintype "bidirectional"))
      (node (ref "SV26") (pin "6") (pinfunction "6_6") (pintype "passive"))
      (node (ref "SV28") (pin "6") (pinfunction "6_6") (pintype "passive"))
    )
    (net (code "73") (name "Net-(4-CHAN14)") (class "Default")
      (node (ref "4") (pin "17") (pinfunction "CHAN14_17") (pintype "bidirectional"))
      (node (ref "SV38") (pin "1") (pinfunction "1_1") (pintype "passive"))
      (node (ref "SV39") (pin "1") (pinfunction "1_1") (pintype "passive"))
    )
    (net (code "74") (name "Net-(4-CHAN15)") (class "Default")
      (node (ref "4") (pin "16") (pinfunction "CHAN15_16") (pintype "bidirectional"))
      (node (ref "SV38") (pin "2") (pinfunction "2_2") (pintype "passive"))
      (node (ref "SV39") (pin "2") (pinfunction "2_2") (pintype "passive"))
    )
    (net (code "75") (name "Net-(4-COM)") (class "Default")
      (node (ref "4") (pin "1") (pinfunction "COM_1") (pintype "bidirectional"))
      (node (ref "R14") (pin "1") (pinfunction "1_1") (pintype "passive"))
      (node (ref "U$5") (pin "6") (pinfunction "CHAN3_6") (pintype "bidirectional"))
    )
    (net (code "76") (name "Net-(5-CHAN0)") (class "Default")
      (node (ref "5") (pin "9") (pinfunction "CHAN0_9") (pintype "bidirectional"))
      (node (ref "SV13") (pin "1") (pinfunction "1_1") (pintype "passive"))
      (node (ref "SV5") (pin "1") (pinfunction "1_1") (pintype "passive"))
    )
    (net (code "77") (name "Net-(5-CHAN1)") (class "Default")
      (node (ref "5") (pin "8") (pinfunction "CHAN1_8") (pintype "bidirectional"))
      (node (ref "SV13") (pin "2") (pinfunction "2_2") (pintype "passive"))
      (node (ref "SV5") (pin "2") (pinfunction "2_2") (pintype "passive"))
    )
    (net (code "78") (name "Net-(5-CHAN2)") (class "Default")
      (node (ref "5") (pin "7") (pinfunction "CHAN2_7") (pintype "bidirectional"))
      (node (ref "SV13") (pin "3") (pinfunction "3_3") (pintype "passive"))
      (node (ref "SV5") (pin "3") (pinfunction "3_3") (pintype "passive"))
    )
    (net (code "79") (name "Net-(5-CHAN3)") (class "Default")
      (node (ref "5") (pin "6") (pinfunction "CHAN3_6") (pintype "bidirectional"))
      (node (ref "SV13") (pin "4") (pinfunction "4_4") (pintype "passive"))
      (node (ref "SV5") (pin "4") (pinfunction "4_4") (pintype "passive"))
    )
    (net (code "80") (name "Net-(5-CHAN4)") (class "Default")
      (node (ref "5") (pin "5") (pinfunction "CHAN4_5") (pintype "bidirectional"))
      (node (ref "SV13") (pin "5") (pinfunction "5_5") (pintype "passive"))
      (node (ref "SV5") (pin "5") (pinfunction "5_5") (pintype "passive"))
    )
    (net (code "81") (name "Net-(5-CHAN5)") (class "Default")
      (node (ref "5") (pin "4") (pinfunction "CHAN5_4") (pintype "bidirectional"))
      (node (ref "SV13") (pin "6") (pinfunction "6_6") (pintype "passive"))
      (node (ref "SV5") (pin "6") (pinfunction "6_6") (pintype "passive"))
    )
    (net (code "82") (name "Net-(5-CHAN6)") (class "Default")
      (node (ref "5") (pin "3") (pinfunction "CHAN6_3") (pintype "bidirectional"))
      (node (ref "SV13") (pin "7") (pinfunction "7_7") (pintype "passive"))
      (node (ref "SV5") (pin "7") (pinfunction "7_7") (pintype "passive"))
    )
    (net (code "83") (name "Net-(5-CHAN7)") (class "Default")
      (node (ref "5") (pin "2") (pinfunction "CHAN7_2") (pintype "bidirectional"))
      (node (ref "SV13") (pin "8") (pinfunction "8_8") (pintype "passive"))
      (node (ref "SV5") (pin "8") (pinfunction "8_8") (pintype "passive"))
    )
    (net (code "84") (name "Net-(5-CHAN8)") (class "Default")
      (node (ref "5") (pin "23") (pinfunction "CHAN8_23") (pintype "bidirectional"))
      (node (ref "SV14") (pin "1") (pinfunction "1_1") (pintype "passive"))
      (node (ref "SV6") (pin "1") (pinfunction "1_1") (pintype "passive"))
    )
    (net (code "85") (name "Net-(5-CHAN9)") (class "Default")
      (node (ref "5") (pin "22") (pinfunction "CHAN9_22") (pintype "bidirectional"))
      (node (ref "SV14") (pin "2") (pinfunction "2_2") (pintype "passive"))
      (node (ref "SV6") (pin "2") (pinfunction "2_2") (pintype "passive"))
    )
    (net (code "86") (name "Net-(5-CHAN10)") (class "Default")
      (node (ref "5") (pin "21") (pinfunction "CHAN10_21") (pintype "bidirectional"))
      (node (ref "SV14") (pin "3") (pinfunction "3_3") (pintype "passive"))
      (node (ref "SV6") (pin "3") (pinfunction "3_3") (pintype "passive"))
    )
    (net (code "87") (name "Net-(5-CHAN11)") (class "Default")
      (node (ref "5") (pin "20") (pinfunction "CHAN11_20") (pintype "bidirectional"))
      (node (ref "SV14") (pin "4") (pinfunction "4_4") (pintype "passive"))
      (node (ref "SV6") (pin "4") (pinfunction "4_4") (pintype "passive"))
    )
    (net (code "88") (name "Net-(5-CHAN12)") (class "Default")
      (node (ref "5") (pin "19") (pinfunction "CHAN12_19") (pintype "bidirectional"))
      (node (ref "SV14") (pin "5") (pinfunction "5_5") (pintype "passive"))
      (node (ref "SV6") (pin "5") (pinfunction "5_5") (pintype "passive"))
    )
    (net (code "89") (name "Net-(5-CHAN13)") (class "Default")
      (node (ref "5") (pin "18") (pinfunction "CHAN13_18") (pintype "bidirectional"))
      (node (ref "SV14") (pin "6") (pinfunction "6_6") (pintype "passive"))
      (node (ref "SV6") (pin "6") (pinfunction "6_6") (pintype "passive"))
    )
    (net (code "90") (name "Net-(5-CHAN14)") (class "Default")
      (node (ref "5") (pin "17") (pinfunction "CHAN14_17") (pintype "bidirectional"))
      (node (ref "SV14") (pin "7") (pinfunction "7_7") (pintype "passive"))
      (node (ref "SV6") (pin "7") (pinfunction "7_7") (pintype "passive"))
    )
    (net (code "91") (name "Net-(5-CHAN15)") (class "Default")
      (node (ref "5") (pin "16") (pinfunction "CHAN15_16") (pintype "bidirectional"))
      (node (ref "SV14") (pin "8") (pinfunction "8_8") (pintype "passive"))
      (node (ref "SV6") (pin "8") (pinfunction "8_8") (pintype "passive"))
    )
    (net (code "92") (name "Net-(5-COM)") (class "Default")
      (node (ref "5") (pin "1") (pinfunction "COM_1") (pintype "bidirectional"))
      (node (ref "R10") (pin "2") (pinfunction "2_2") (pintype "passive"))
      (node (ref "U$5") (pin "5") (pinfunction "CHAN4_5") (pintype "bidirectional"))
    )
    (net (code "93") (name "Net-(6-CHAN0)") (class "Default")
      (node (ref "6") (pin "9") (pinfunction "CHAN0_9") (pintype "bidirectional"))
      (node (ref "SV15") (pin "1") (pinfunction "1_1") (pintype "passive"))
      (node (ref "SV7") (pin "1") (pinfunction "1_1") (pintype "passive"))
    )
    (net (code "94") (name "Net-(6-CHAN1)") (class "Default")
      (node (ref "6") (pin "8") (pinfunction "CHAN1_8") (pintype "bidirectional"))
      (node (ref "SV15") (pin "2") (pinfunction "2_2") (pintype "passive"))
      (node (ref "SV7") (pin "2") (pinfunction "2_2") (pintype "passive"))
    )
    (net (code "95") (name "Net-(6-CHAN2)") (class "Default")
      (node (ref "6") (pin "7") (pinfunction "CHAN2_7") (pintype "bidirectional"))
      (node (ref "SV15") (pin "3") (pinfunction "3_3") (pintype "passive"))
      (node (ref "SV7") (pin "3") (pinfunction "3_3") (pintype "passive"))
    )
    (net (code "96") (name "Net-(6-CHAN3)") (class "Default")
      (node (ref "6") (pin "6") (pinfunction "CHAN3_6") (pintype "bidirectional"))
      (node (ref "SV15") (pin "4") (pinfunction "4_4") (pintype "passive"))
      (node (ref "SV7") (pin "4") (pinfunction "4_4") (pintype "passive"))
    )
    (net (code "97") (name "Net-(6-CHAN4)") (class "Default")
      (node (ref "6") (pin "5") (pinfunction "CHAN4_5") (pintype "bidirectional"))
      (node (ref "SV15") (pin "5") (pinfunction "5_5") (pintype "passive"))
      (node (ref "SV7") (pin "5") (pinfunction "5_5") (pintype "passive"))
    )
    (net (code "98") (name "Net-(6-CHAN5)") (class "Default")
      (node (ref "6") (pin "4") (pinfunction "CHAN5_4") (pintype "bidirectional"))
      (node (ref "SV15") (pin "6") (pinfunction "6_6") (pintype "passive"))
      (node (ref "SV7") (pin "6") (pinfunction "6_6") (pintype "passive"))
    )
    (net (code "99") (name "Net-(6-CHAN6)") (class "Default")
      (node (ref "6") (pin "3") (pinfunction "CHAN6_3") (pintype "bidirectional"))
      (node (ref "SV15") (pin "7") (pinfunction "7_7") (pintype "passive"))
      (node (ref "SV7") (pin "7") (pinfunction "7_7") (pintype "passive"))
    )
    (net (code "100") (name "Net-(6-CHAN7)") (class "Default")
      (node (ref "6") (pin "2") (pinfunction "CHAN7_2") (pintype "bidirectional"))
      (node (ref "SV15") (pin "8") (pinfunction "8_8") (pintype "passive"))
      (node (ref "SV7") (pin "8") (pinfunction "8_8") (pintype "passive"))
    )
    (net (code "101") (name "Net-(6-CHAN8)") (class "Default")
      (node (ref "6") (pin "23") (pinfunction "CHAN8_23") (pintype "bidirectional"))
      (node (ref "SV16") (pin "1") (pinfunction "1_1") (pintype "passive"))
      (node (ref "SV8") (pin "1") (pinfunction "1_1") (pintype "passive"))
    )
    (net (code "102") (name "Net-(6-CHAN9)") (class "Default")
      (node (ref "6") (pin "22") (pinfunction "CHAN9_22") (pintype "bidirectional"))
      (node (ref "SV16") (pin "2") (pinfunction "2_2") (pintype "passive"))
      (node (ref "SV8") (pin "2") (pinfunction "2_2") (pintype "passive"))
    )
    (net (code "103") (name "Net-(6-CHAN10)") (class "Default")
      (node (ref "6") (pin "21") (pinfunction "CHAN10_21") (pintype "bidirectional"))
      (node (ref "SV16") (pin "3") (pinfunction "3_3") (pintype "passive"))
      (node (ref "SV8") (pin "3") (pinfunction "3_3") (pintype "passive"))
    )
    (net (code "104") (name "Net-(6-CHAN11)") (class "Default")
      (node (ref "6") (pin "20") (pinfunction "CHAN11_20") (pintype "bidirectional"))
      (node (ref "SV16") (pin "4") (pinfunction "4_4") (pintype "passive"))
      (node (ref "SV8") (pin "4") (pinfunction "4_4") (pintype "passive"))
    )
    (net (code "105") (name "Net-(6-CHAN12)") (class "Default")
      (node (ref "6") (pin "19") (pinfunction "CHAN12_19") (pintype "bidirectional"))
      (node (ref "SV16") (pin "5") (pinfunction "5_5") (pintype "passive"))
      (node (ref "SV8") (pin "5") (pinfunction "5_5") (pintype "passive"))
    )
    (net (code "106") (name "Net-(6-CHAN13)") (class "Default")
      (node (ref "6") (pin "18") (pinfunction "CHAN13_18") (pintype "bidirectional"))
      (node (ref "SV16") (pin "6") (pinfunction "6_6") (pintype "passive"))
      (node (ref "SV8") (pin "6") (pinfunction "6_6") (pintype "passive"))
    )
    (net (code "107") (name "Net-(6-CHAN14)") (class "Default")
      (node (ref "6") (pin "17") (pinfunction "CHAN14_17") (pintype "bidirectional"))
      (node (ref "SV16") (pin "7") (pinfunction "7_7") (pintype "passive"))
      (node (ref "SV8") (pin "7") (pinfunction "7_7") (pintype "passive"))
    )
    (net (code "108") (name "Net-(6-CHAN15)") (class "Default")
      (node (ref "6") (pin "16") (pinfunction "CHAN15_16") (pintype "bidirectional"))
      (node (ref "SV16") (pin "8") (pinfunction "8_8") (pintype "passive"))
      (node (ref "SV8") (pin "8") (pinfunction "8_8") (pintype "passive"))
    )
    (net (code "109") (name "Net-(6-COM)") (class "Default")
      (node (ref "6") (pin "1") (pinfunction "COM_1") (pintype "bidirectional"))
      (node (ref "R11") (pin "2") (pinfunction "2_2") (pintype "passive"))
      (node (ref "U$5") (pin "4") (pinfunction "CHAN5_4") (pintype "bidirectional"))
    )
    (net (code "110") (name "Net-(7-CHAN0)") (class "Default")
      (node (ref "7") (pin "9") (pinfunction "CHAN0_9") (pintype "bidirectional"))
      (node (ref "SV21") (pin "1") (pinfunction "1_1") (pintype "passive"))
      (node (ref "SV23") (pin "1") (pinfunction "1_1") (pintype "passive"))
    )
    (net (code "111") (name "Net-(7-CHAN1)") (class "Default")
      (node (ref "7") (pin "8") (pinfunction "CHAN1_8") (pintype "bidirectional"))
      (node (ref "SV21") (pin "2") (pinfunction "2_2") (pintype "passive"))
      (node (ref "SV23") (pin "2") (pinfunction "2_2") (pintype "passive"))
    )
    (net (code "112") (name "Net-(7-CHAN2)") (class "Default")
      (node (ref "7") (pin "7") (pinfunction "CHAN2_7") (pintype "bidirectional"))
      (node (ref "SV21") (pin "3") (pinfunction "3_3") (pintype "passive"))
      (node (ref "SV23") (pin "3") (pinfunction "3_3") (pintype "passive"))
    )
    (net (code "113") (name "Net-(7-CHAN3)") (class "Default")
      (node (ref "7") (pin "6") (pinfunction "CHAN3_6") (pintype "bidirectional"))
      (node (ref "SV21") (pin "4") (pinfunction "4_4") (pintype "passive"))
      (node (ref "SV23") (pin "4") (pinfunction "4_4") (pintype "passive"))
    )
    (net (code "114") (name "Net-(7-CHAN4)") (class "Default")
      (node (ref "7") (pin "5") (pinfunction "CHAN4_5") (pintype "bidirectional"))
      (node (ref "SV21") (pin "5") (pinfunction "5_5") (pintype "passive"))
      (node (ref "SV23") (pin "5") (pinfunction "5_5") (pintype "passive"))
    )
    (net (code "115") (name "Net-(7-CHAN5)") (class "Default")
      (node (ref "7") (pin "4") (pinfunction "CHAN5_4") (pintype "bidirectional"))
      (node (ref "SV21") (pin "6") (pinfunction "6_6") (pintype "passive"))
      (node (ref "SV23") (pin "6") (pinfunction "6_6") (pintype "passive"))
    )
    (net (code "116") (name "Net-(7-CHAN6)") (class "Default")
      (node (ref "7") (pin "3") (pinfunction "CHAN6_3") (pintype "bidirectional"))
      (node (ref "SV21") (pin "7") (pinfunction "7_7") (pintype "passive"))
      (node (ref "SV23") (pin "7") (pinfunction "7_7") (pintype "passive"))
    )
    (net (code "117") (name "Net-(7-CHAN7)") (class "Default")
      (node (ref "7") (pin "2") (pinfunction "CHAN7_2") (pintype "bidirectional"))
      (node (ref "SV21") (pin "8") (pinfunction "8_8") (pintype "passive"))
      (node (ref "SV23") (pin "8") (pinfunction "8_8") (pintype "passive"))
    )
    (net (code "118") (name "Net-(7-CHAN8)") (class "Default")
      (node (ref "7") (pin "23") (pinfunction "CHAN8_23") (pintype "bidirectional"))
      (node (ref "SV22") (pin "1") (pinfunction "1_1") (pintype "passive"))
      (node (ref "SV24") (pin "1") (pinfunction "1_1") (pintype "passive"))
    )
    (net (code "119") (name "Net-(7-CHAN9)") (class "Default")
      (node (ref "7") (pin "22") (pinfunction "CHAN9_22") (pintype "bidirectional"))
      (node (ref "SV22") (pin "2") (pinfunction "2_2") (pintype "passive"))
      (node (ref "SV24") (pin "2") (pinfunction "2_2") (pintype "passive"))
    )
    (net (code "120") (name "Net-(7-CHAN10)") (class "Default")
      (node (ref "7") (pin "21") (pinfunction "CHAN10_21") (pintype "bidirectional"))
      (node (ref "SV22") (pin "3") (pinfunction "3_3") (pintype "passive"))
      (node (ref "SV24") (pin "3") (pinfunction "3_3") (pintype "passive"))
    )
    (net (code "121") (name "Net-(7-CHAN11)") (class "Default")
      (node (ref "7") (pin "20") (pinfunction "CHAN11_20") (pintype "bidirectional"))
      (node (ref "SV22") (pin "4") (pinfunction "4_4") (pintype "passive"))
      (node (ref "SV24") (pin "4") (pinfunction "4_4") (pintype "passive"))
    )
    (net (code "122") (name "Net-(7-CHAN12)") (class "Default")
      (node (ref "7") (pin "19") (pinfunction "CHAN12_19") (pintype "bidirectional"))
      (node (ref "SV22") (pin "5") (pinfunction "5_5") (pintype "passive"))
      (node (ref "SV24") (pin "5") (pinfunction "5_5") (pintype "passive"))
    )
    (net (code "123") (name "Net-(7-CHAN13)") (class "Default")
      (node (ref "7") (pin "18") (pinfunction "CHAN13_18") (pintype "bidirectional"))
      (node (ref "SV22") (pin "6") (pinfunction "6_6") (pintype "passive"))
      (node (ref "SV24") (pin "6") (pinfunction "6_6") (pintype "passive"))
    )
    (net (code "124") (name "Net-(7-CHAN14)") (class "Default")
      (node (ref "7") (pin "17") (pinfunction "CHAN14_17") (pintype "bidirectional"))
      (node (ref "SV22") (pin "7") (pinfunction "7_7") (pintype "passive"))
      (node (ref "SV24") (pin "7") (pinfunction "7_7") (pintype "passive"))
    )
    (net (code "125") (name "Net-(7-CHAN15)") (class "Default")
      (node (ref "7") (pin "16") (pinfunction "CHAN15_16") (pintype "bidirectional"))
      (node (ref "SV22") (pin "8") (pinfunction "8_8") (pintype "passive"))
      (node (ref "SV24") (pin "8") (pinfunction "8_8") (pintype "passive"))
    )
    (net (code "126") (name "Net-(7-COM)") (class "Default")
      (node (ref "7") (pin "1") (pinfunction "COM_1") (pintype "bidirectional"))
      (node (ref "R12") (pin "2") (pinfunction "2_2") (pintype "passive"))
      (node (ref "U$5") (pin "3") (pinfunction "CHAN6_3") (pintype "bidirectional"))
    )
    (net (code "127") (name "Net-(8-CHAN0)") (class "Default")
      (node (ref "8") (pin "9") (pinfunction "CHAN0_9") (pintype "bidirectional"))
      (node (ref "SV29") (pin "1") (pinfunction "1_1") (pintype "passive"))
      (node (ref "SV31") (pin "1") (pinfunction "1_1") (pintype "passive"))
    )
    (net (code "128") (name "Net-(8-CHAN1)") (class "Default")
      (node (ref "8") (pin "8") (pinfunction "CHAN1_8") (pintype "bidirectional"))
      (node (ref "SV29") (pin "2") (pinfunction "2_2") (pintype "passive"))
      (node (ref "SV31") (pin "2") (pinfunction "2_2") (pintype "passive"))
    )
    (net (code "129") (name "Net-(8-CHAN2)") (class "Default")
      (node (ref "8") (pin "7") (pinfunction "CHAN2_7") (pintype "bidirectional"))
      (node (ref "SV29") (pin "3") (pinfunction "3_3") (pintype "passive"))
      (node (ref "SV31") (pin "3") (pinfunction "3_3") (pintype "passive"))
    )
    (net (code "130") (name "Net-(8-CHAN3)") (class "Default")
      (node (ref "8") (pin "6") (pinfunction "CHAN3_6") (pintype "bidirectional"))
      (node (ref "SV29") (pin "4") (pinfunction "4_4") (pintype "passive"))
      (node (ref "SV31") (pin "4") (pinfunction "4_4") (pintype "passive"))
    )
    (net (code "131") (name "Net-(8-CHAN4)") (class "Default")
      (node (ref "8") (pin "5") (pinfunction "CHAN4_5") (pintype "bidirectional"))
      (node (ref "SV29") (pin "5") (pinfunction "5_5") (pintype "passive"))
      (node (ref "SV31") (pin "5") (pinfunction "5_5") (pintype "passive"))
    )
    (net (code "132") (name "Net-(8-CHAN5)") (class "Default")
      (node (ref "8") (pin "4") (pinfunction "CHAN5_4") (pintype "bidirectional"))
      (node (ref "SV29") (pin "6") (pinfunction "6_6") (pintype "passive"))
      (node (ref "SV31") (pin "6") (pinfunction "6_6") (pintype "passive"))
    )
    (net (code "133") (name "Net-(8-CHAN6)") (class "Default")
      (node (ref "8") (pin "3") (pinfunction "CHAN6_3") (pintype "bidirectional"))
      (node (ref "SV29") (pin "7") (pinfunction "7_7") (pintype "passive"))
      (node (ref "SV31") (pin "7") (pinfunction "7_7") (pintype "passive"))
    )
    (net (code "134") (name "Net-(8-CHAN7)") (class "Default")
      (node (ref "8") (pin "2") (pinfunction "CHAN7_2") (pintype "bidirectional"))
      (node (ref "SV29") (pin "8") (pinfunction "8_8") (pintype "passive"))
      (node (ref "SV31") (pin "8") (pinfunction "8_8") (pintype "passive"))
    )
    (net (code "135") (name "Net-(8-CHAN8)") (class "Default")
      (node (ref "8") (pin "23") (pinfunction "CHAN8_23") (pintype "bidirectional"))
      (node (ref "SV30") (pin "1") (pinfunction "1_1") (pintype "passive"))
      (node (ref "SV32") (pin "1") (pinfunction "1_1") (pintype "passive"))
    )
    (net (code "136") (name "Net-(8-CHAN9)") (class "Default")
      (node (ref "8") (pin "22") (pinfunction "CHAN9_22") (pintype "bidirectional"))
      (node (ref "SV30") (pin "2") (pinfunction "2_2") (pintype "passive"))
      (node (ref "SV32") (pin "2") (pinfunction "2_2") (pintype "passive"))
    )
    (net (code "137") (name "Net-(8-CHAN10)") (class "Default")
      (node (ref "8") (pin "21") (pinfunction "CHAN10_21") (pintype "bidirectional"))
      (node (ref "SV30") (pin "3") (pinfunction "3_3") (pintype "passive"))
      (node (ref "SV32") (pin "3") (pinfunction "3_3") (pintype "passive"))
    )
    (net (code "138") (name "Net-(8-CHAN11)") (class "Default")
      (node (ref "8") (pin "20") (pinfunction "CHAN11_20") (pintype "bidirectional"))
      (node (ref "SV30") (pin "4") (pinfunction "4_4") (pintype "passive"))
      (node (ref "SV32") (pin "4") (pinfunction "4_4") (pintype "passive"))
    )
    (net (code "139") (name "Net-(8-CHAN12)") (class "Default")
      (node (ref "8") (pin "19") (pinfunction "CHAN12_19") (pintype "bidirectional"))
      (node (ref "SV33") (pin "1") (pinfunction "1_1") (pintype "passive"))
      (node (ref "SV34") (pin "1") (pinfunction "1_1") (pintype "passive"))
    )
    (net (code "140") (name "Net-(8-CHAN13)") (class "Default")
      (node (ref "8") (pin "18") (pinfunction "CHAN13_18") (pintype "bidirectional"))
      (node (ref "SV33") (pin "2") (pinfunction "2_2") (pintype "passive"))
      (node (ref "SV34") (pin "2") (pinfunction "2_2") (pintype "passive"))
    )
    (net (code "141") (name "Net-(8-CHAN14)") (class "Default")
      (node (ref "8") (pin "17") (pinfunction "CHAN14_17") (pintype "bidirectional"))
      (node (ref "SV35") (pin "1") (pinfunction "1_1") (pintype "passive"))
      (node (ref "SV36") (pin "1") (pinfunction "1_1") (pintype "passive"))
    )
    (net (code "142") (name "Net-(8-CHAN15)") (class "Default")
      (node (ref "8") (pin "16") (pinfunction "CHAN15_16") (pintype "bidirectional"))
      (node (ref "SV35") (pin "2") (pinfunction "2_2") (pintype "passive"))
      (node (ref "SV36") (pin "2") (pinfunction "2_2") (pintype "passive"))
    )
    (net (code "143") (name "Net-(8-COM)") (class "Default")
      (node (ref "8") (pin "1") (pinfunction "COM_1") (pintype "bidirectional"))
      (node (ref "R6") (pin "2") (pinfunction "2_2") (pintype "passive"))
      (node (ref "U$5") (pin "2") (pinfunction "CHAN7_2") (pintype "bidirectional"))
    )
    (net (code "144") (name "Net-(U$5-COM)") (class "Default")
      (node (ref "MAIN") (pin "6") (pinfunction "6_6") (pintype "passive"))
      (node (ref "R13") (pin "2") (pinfunction "2_2") (pintype "passive"))
      (node (ref "U$5") (pin "1") (pinfunction "COM_1") (pintype "bidirectional"))
    )
    (net (code "145") (name "Net-(U$5-S0)") (class "Default")
      (node (ref "MAIN") (pin "2") (pinfunction "2_2") (pintype "passive"))
      (node (ref "U$5") (pin "10") (pinfunction "S0_10") (pintype "input"))
    )
    (net (code "146") (name "Net-(U$5-S1)") (class "Default")
      (node (ref "MAIN") (pin "3") (pinfunction "3_3") (pintype "passive"))
      (node (ref "U$5") (pin "11") (pinfunction "S1_11") (pintype "input"))
    )
    (net (code "147") (name "Net-(U$5-S2)") (class "Default")
      (node (ref "MAIN") (pin "4") (pinfunction "4_4") (pintype "passive"))
      (node (ref "U$5") (pin "14") (pinfunction "S2_14") (pintype "input"))
    )
    (net (code "148") (name "Net-(U$5-S3)") (class "Default")
      (node (ref "MAIN") (pin "5") (pinfunction "5_5") (pintype "passive"))
      (node (ref "U$5") (pin "13") (pinfunction "S3_13") (pintype "input"))
    )
    (net (code "149") (name "unconnected-(U$5-CHAN8-Pad23)") (class "Default")
      (node (ref "U$5") (pin "23") (pinfunction "CHAN8_23") (pintype "bidirectional"))
    )
    (net (code "150") (name "unconnected-(U$5-CHAN9-Pad22)") (class "Default")
      (node (ref "U$5") (pin "22") (pinfunction "CHAN9_22") (pintype "bidirectional"))
    )
    (net (code "151") (name "unconnected-(U$5-CHAN10-Pad21)") (class "Default")
      (node (ref "U$5") (pin "21") (pinfunction "CHAN10_21") (pintype "bidirectional"))
    )
    (net (code "152") (name "unconnected-(U$5-CHAN11-Pad20)") (class "Default")
      (node (ref "U$5") (pin "20") (pinfunction "CHAN11_20") (pintype "bidirectional"))
    )
    (net (code "153") (name "unconnected-(U$5-CHAN12-Pad19)") (class "Default")
      (node (ref "U$5") (pin "19") (pinfunction "CHAN12_19") (pintype "bidirectional"))
    )
    (net (code "154") (name "unconnected-(U$5-CHAN13-Pad18)") (class "Default")
      (node (ref "U$5") (pin "18") (pinfunction "CHAN13_18") (pintype "bidirectional"))
    )
    (net (code "155") (name "unconnected-(U$5-CHAN14-Pad17)") (class "Default")
      (node (ref "U$5") (pin "17") (pinfunction "CHAN14_17") (pintype "bidirectional"))
    )
    (net (code "156") (name "unconnected-(U$5-CHAN15-Pad16)") (class "Default")
      (node (ref "U$5") (pin "16") (pinfunction "CHAN15_16") (pintype "bidirectional"))
    )
  )
)
